# power_input.net
KiCad netlist of a schematic drawn in Altium Designer
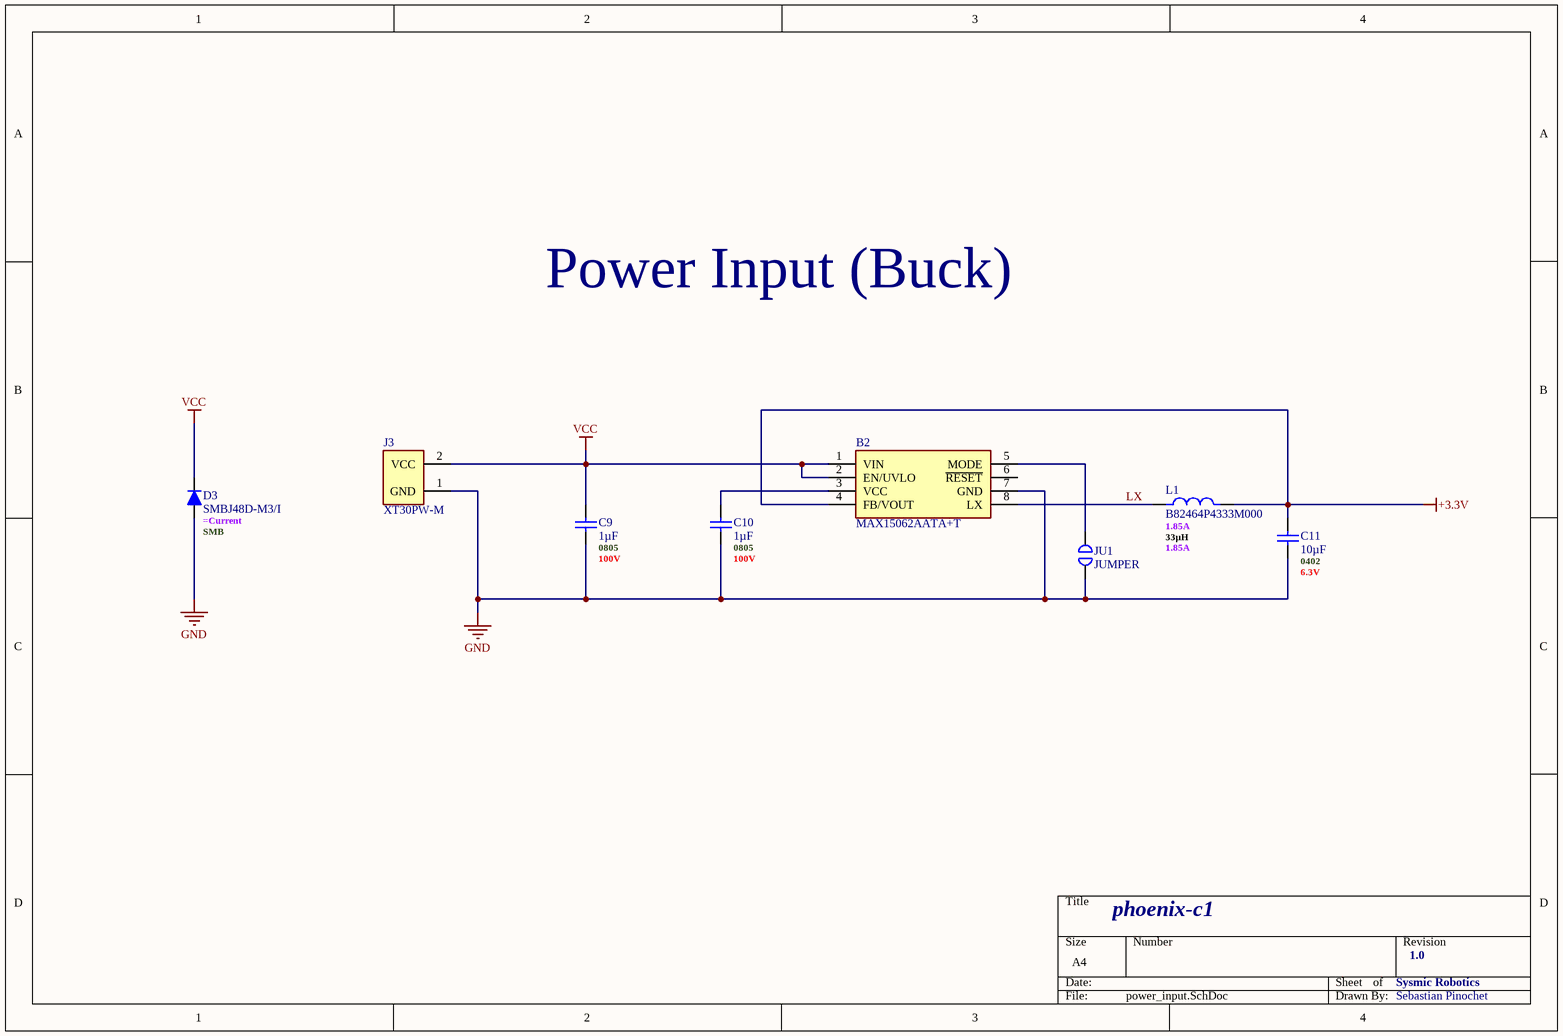
[diagram p0: power_input.SchDoc]

(export (version "E")
  (design (tool "Eeschema 10.0.6"))
  (components
    (comp (ref "B2")
      (value "MAX15062AATA+T")
      (footprint "8-TDFN - ANALOG")
      (description "Step-Down 60V, 300mA, Ultra-Small, High-Efficiency, Synchronous  DC-DC Converters")
      (fields (field (name "MOUSER PART NUMBER") "700-MAX15062AATA+T"))
      (libsource (lib "IC - MAX15062AATA+T") (part "MAX15062AATA+T"))
    )
    (comp (ref "C9")
      (value "1µF")
      (footprint "C0805 - MURATA")
      (description "Ceramic Capacitor, Ceramic, 100V, 10% +Tol, 10% -Tol, X7S, 22% TC, 1uF, Surface Mount, 0805")
      (fields
        (field (name "MANUFACTURER") "Murata")
        (field (name "MANUFACTURER PART NUMBER") "GCM21BC72A105KE36L")
        (field (name ".CASE/PACKAGE") "0805")
        (field (name ".VOLTAGE RATING (DC)") "100V")
      )
      (libsource (lib "CAP - GCM21BC72A105KE36L") (part "GCM21BC72A105KE36L"))
    )
    (comp (ref "C10")
      (value "1µF")
      (footprint "C0805 - MURATA")
      (description "Ceramic Capacitor, Ceramic, 100V, 10% +Tol, 10% -Tol, X7S, 22% TC, 1uF, Surface Mount, 0805")
      (fields
        (field (name "MANUFACTURER") "Murata")
        (field (name "MANUFACTURER PART NUMBER") "GCM21BC72A105KE36L")
        (field (name ".CASE/PACKAGE") "0805")
        (field (name ".VOLTAGE RATING (DC)") "100V")
      )
      (libsource (lib "CAP - GCM21BC72A105KE36L") (part "GCM21BC72A105KE36L"))
    )
    (comp (ref "C11")
      (value "10µF")
      (footprint "C0402 - MURATA")
      (description "Ceramic Capacitor, Ceramic, 6.3V, 20% +Tol, 20% -Tol, X5R, 15% TC, 10uF, Surface Mount, 0402")
      (fields
        (field (name "MANUFACTURER") "Murata")
        (field (name "MANUFACTURER PART NUMBER") "GRM155R60J106ME05D")
        (field (name ".CASE/PACKAGE") "0402")
        (field (name ".VOLTAGE RATING (DC)") "6.3V")
      )
      (libsource (lib "CAP - GRM155R60J106ME05D") (part "GRM155R60J106ME05D"))
    )
    (comp (ref "D3")
      (value "SMBJ48D-M3/I")
      (footprint "DDO-214AA (SMBJ) - VISHAY")
      (description "Trans Voltage Suppressor Diode, 600W, 48V V(RWM), Unidirectional, 1 Element, Silicon, DO-214AA")
      (fields (field (name "MANUFACTURER") "Vishay") (field (name ".CASE/PACKAGE") "SMB"))
      (libsource (lib "DIODE - SMBJ48D-M31") (part "SMBJ48D-M3/I"))
    )
    (comp (ref "J3")
      (value "XT30PW-M")
      (footprint "CONN - XT30PW-M")
      (description "30A Low Temperature Rise Fire Retardant Plug")
      (libsource (lib "CONN - XT30PW-M") (part "XT30PW-M"))
    )
    (comp (ref "JU1") (value "JUMPER") (footprint "JUMPER") (libsource (lib "JUMPER") (part "JUMPER")))
    (comp (ref "L1")
      (value "B82464P4333M000")
      (footprint "SRN4018-330M")
      (description "General Purpose Inductor, 33uH, 20%, 1 Element, Ferrite-Core, SMD, 1515")
      (fields
        (field (name "MANUFACTURER") "EPCOS")
        (field (name "TOLERANCE") "20%")
        (field (name ".RMS CURRENT (IRMS)") "1.85A")
        (field (name ".VALUE") "33µH")
        (field (name ".MAX DC CURRENT") "1.85A")
      )
      (libsource (lib "IND - LPS4018-333MRC") (part "LPS4018-333MRC"))
    )
  )
  (nets
    (net (code "1") (name "+3.3V") (class "Default")
      (node (ref "B2") (pin "4") (pinfunction "FB/VOUT_4") (pintype "passive"))
      (node (ref "C11") (pin "2") (pinfunction "2_2") (pintype "passive"))
      (node (ref "L1") (pin "2") (pinfunction "2_2") (pintype "passive"))
    )
    (net (code "2") (name "/LX") (class "Default")
      (node (ref "B2") (pin "8") (pinfunction "LX_8") (pintype "passive"))
      (node (ref "L1") (pin "1") (pinfunction "1_1") (pintype "passive"))
    )
    (net (code "3") (name "GND") (class "Default")
      (node (ref "B2") (pin "7") (pinfunction "GND_7") (pintype "passive"))
      (node (ref "C10") (pin "1") (pinfunction "1_1") (pintype "passive"))
      (node (ref "C11") (pin "1") (pinfunction "1_1") (pintype "passive"))
      (node (ref "C9") (pin "1") (pinfunction "1_1") (pintype "passive"))
      (node (ref "D3") (pin "2") (pinfunction "2_2") (pintype "passive"))
      (node (ref "J3") (pin "1") (pinfunction "GND_1") (pintype "passive"))
      (node (ref "JU1") (pin "1") (pinfunction "1_1") (pintype "passive"))
    )
    (net (code "4") (name "Net-(B2-MODE)") (class "Default")
      (node (ref "B2") (pin "5") (pinfunction "MODE_5") (pintype "passive"))
      (node (ref "JU1") (pin "2") (pinfunction "2_2") (pintype "passive"))
    )
    (net (code "5") (name "Net-(B2-VCC)") (class "Default")
      (node (ref "B2") (pin "3") (pinfunction "VCC_3") (pintype "passive"))
      (node (ref "C10") (pin "2") (pinfunction "2_2") (pintype "passive"))
    )
    (net (code "6") (name "VCC") (class "Default")
      (node (ref "B2") (pin "1") (pinfunction "VIN_1") (pintype "passive"))
      (node (ref "B2") (pin "2") (pinfunction "EN/UVLO_2") (pintype "passive"))
      (node (ref "C9") (pin "2") (pinfunction "2_2") (pintype "passive"))
      (node (ref "D3") (pin "1") (pinfunction "1_1") (pintype "passive"))
      (node (ref "J3") (pin "2") (pinfunction "VCC_2") (pintype "passive"))
    )
    (net (code "7") (name "unconnected-(B2-~{RESET}-Pad6)") (class "Default")
      (node (ref "B2") (pin "6") (pinfunction "~{RESET}_6") (pintype "passive"))
    )
  )
)
